# ESD-HISTORY.net
KiCad netlist of a schematic drawn in Altium Designer
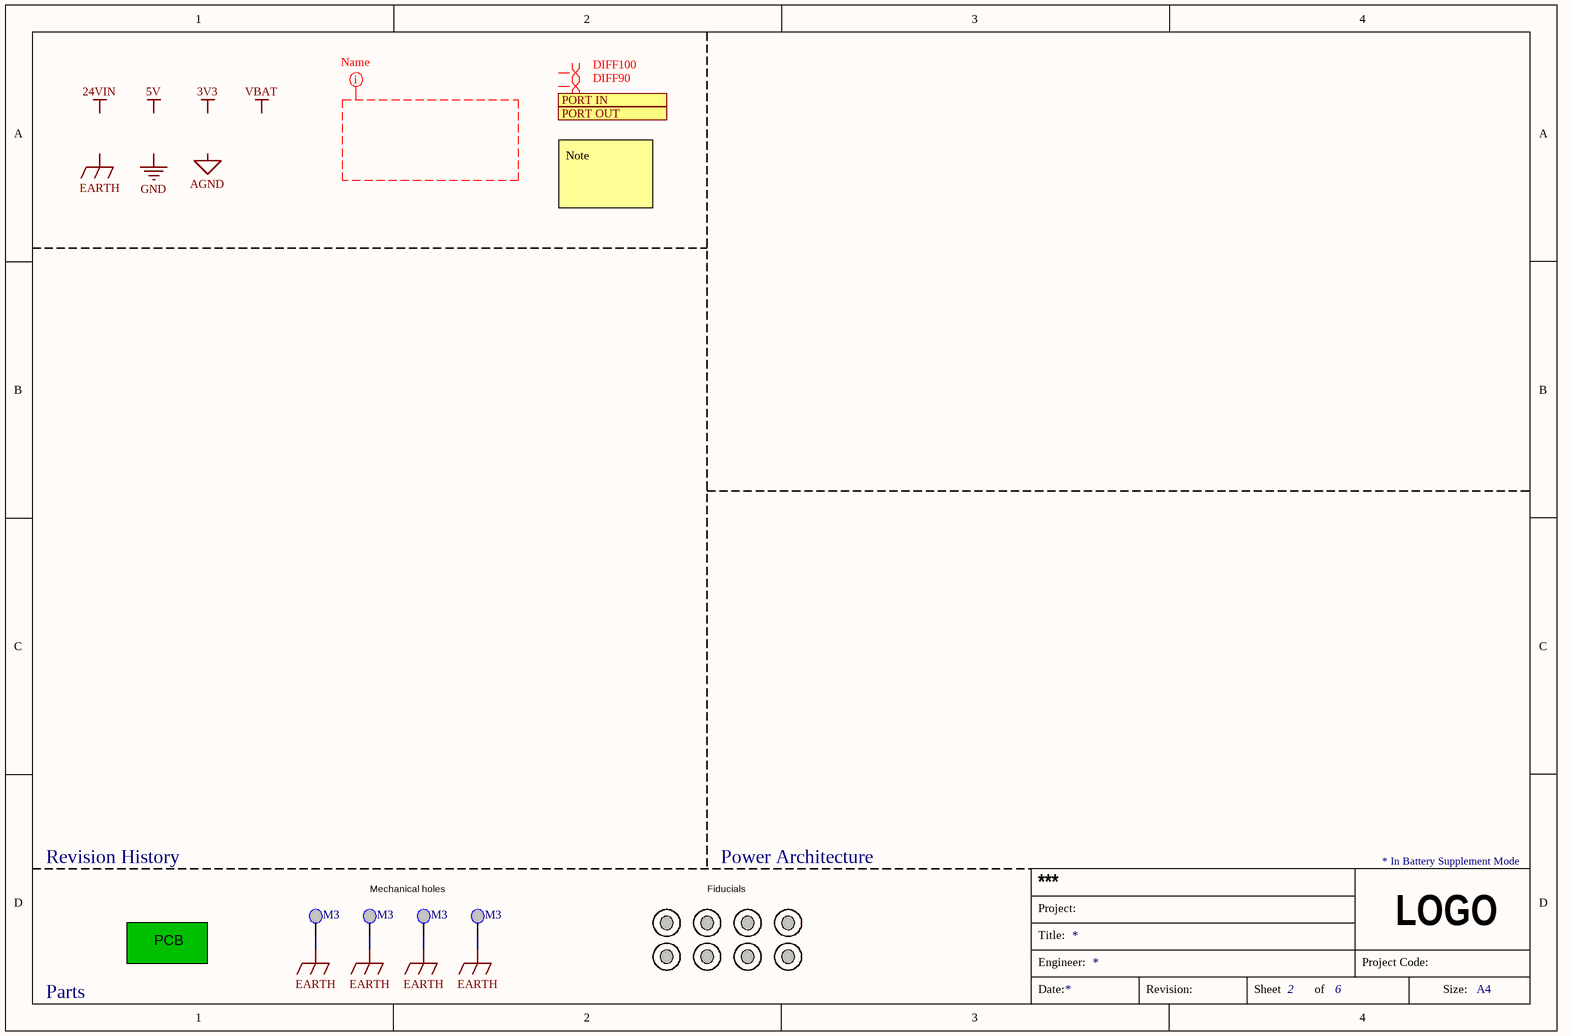
[diagram p0: ESD-HISTORY.SchDoc]

(export (version "E")
  (design (tool "Eeschema 10.0.6"))
  (components
    (comp (ref "FD1")
      (value "Fiducial 1.3")
      (footprint "Fiducial 1.3mm")
      (description "Fiducial 1.3mm")
      (libsource (lib "Miscelaneos") (part "Fiducial 1.3"))
    )
    (comp (ref "FD2")
      (value "Fiducial 1.3")
      (footprint "Fiducial 1.3mm")
      (description "Fiducial 1.3mm")
      (libsource (lib "Miscelaneos") (part "Fiducial 1.3"))
    )
    (comp (ref "FD3")
      (value "Fiducial 1.3")
      (footprint "Fiducial 1.3mm")
      (description "Fiducial 1.3mm")
      (libsource (lib "Miscelaneos") (part "Fiducial 1.3"))
    )
    (comp (ref "FD4")
      (value "Fiducial 1.3")
      (footprint "Fiducial 1.3mm")
      (description "Fiducial 1.3mm")
      (libsource (lib "Miscelaneos") (part "Fiducial 1.3"))
    )
    (comp (ref "FD5")
      (value "Fiducial 1.3")
      (footprint "Fiducial 1.3mm")
      (description "Fiducial 1.3mm")
      (libsource (lib "Miscelaneos") (part "Fiducial 1.3"))
    )
    (comp (ref "FD6")
      (value "Fiducial 1.3")
      (footprint "Fiducial 1.3mm")
      (description "Fiducial 1.3mm")
      (libsource (lib "Miscelaneos") (part "Fiducial 1.3"))
    )
    (comp (ref "FD7")
      (value "Fiducial 1.3")
      (footprint "Fiducial 1.3mm")
      (description "Fiducial 1.3mm")
      (libsource (lib "Miscelaneos") (part "Fiducial 1.3"))
    )
    (comp (ref "FD8")
      (value "Fiducial 1.3")
      (footprint "Fiducial 1.3mm")
      (description "Fiducial 1.3mm")
      (libsource (lib "Miscelaneos") (part "Fiducial 1.3"))
    )
    (comp (ref "MEC1")
      (value "M3")
      (footprint "M3 hole")
      (description "M3 hole")
      (libsource (lib "Miscelaneos") (part "M3 hole"))
    )
    (comp (ref "MEC2")
      (value "M3")
      (footprint "M3 hole")
      (description "M3 hole")
      (libsource (lib "Miscelaneos") (part "M3 hole"))
    )
    (comp (ref "MEC3")
      (value "M3")
      (footprint "M3 hole")
      (description "M3 hole")
      (libsource (lib "Miscelaneos") (part "M3 hole"))
    )
    (comp (ref "MEC4")
      (value "M3")
      (footprint "M3 hole")
      (description "M3 hole")
      (libsource (lib "Miscelaneos") (part "M3 hole"))
    )
    (comp (ref "_PCB1") (value "PCB spec") (description "PCB") (libsource (lib "Miscellaneous") (part "PCB")))
  )
  (nets
    (net (code "7") (name "EARTH") (class "Default")
      (node (ref "MEC1") (pin "0") (pinfunction "0_0") (pintype "passive"))
      (node (ref "MEC2") (pin "0") (pinfunction "0_0") (pintype "passive"))
      (node (ref "MEC3") (pin "0") (pinfunction "0_0") (pintype "passive"))
      (node (ref "MEC4") (pin "0") (pinfunction "0_0") (pintype "passive"))
    )
  )
)
